# LTC5584.net
KiCad netlist of a schematic drawn in Altium Designer
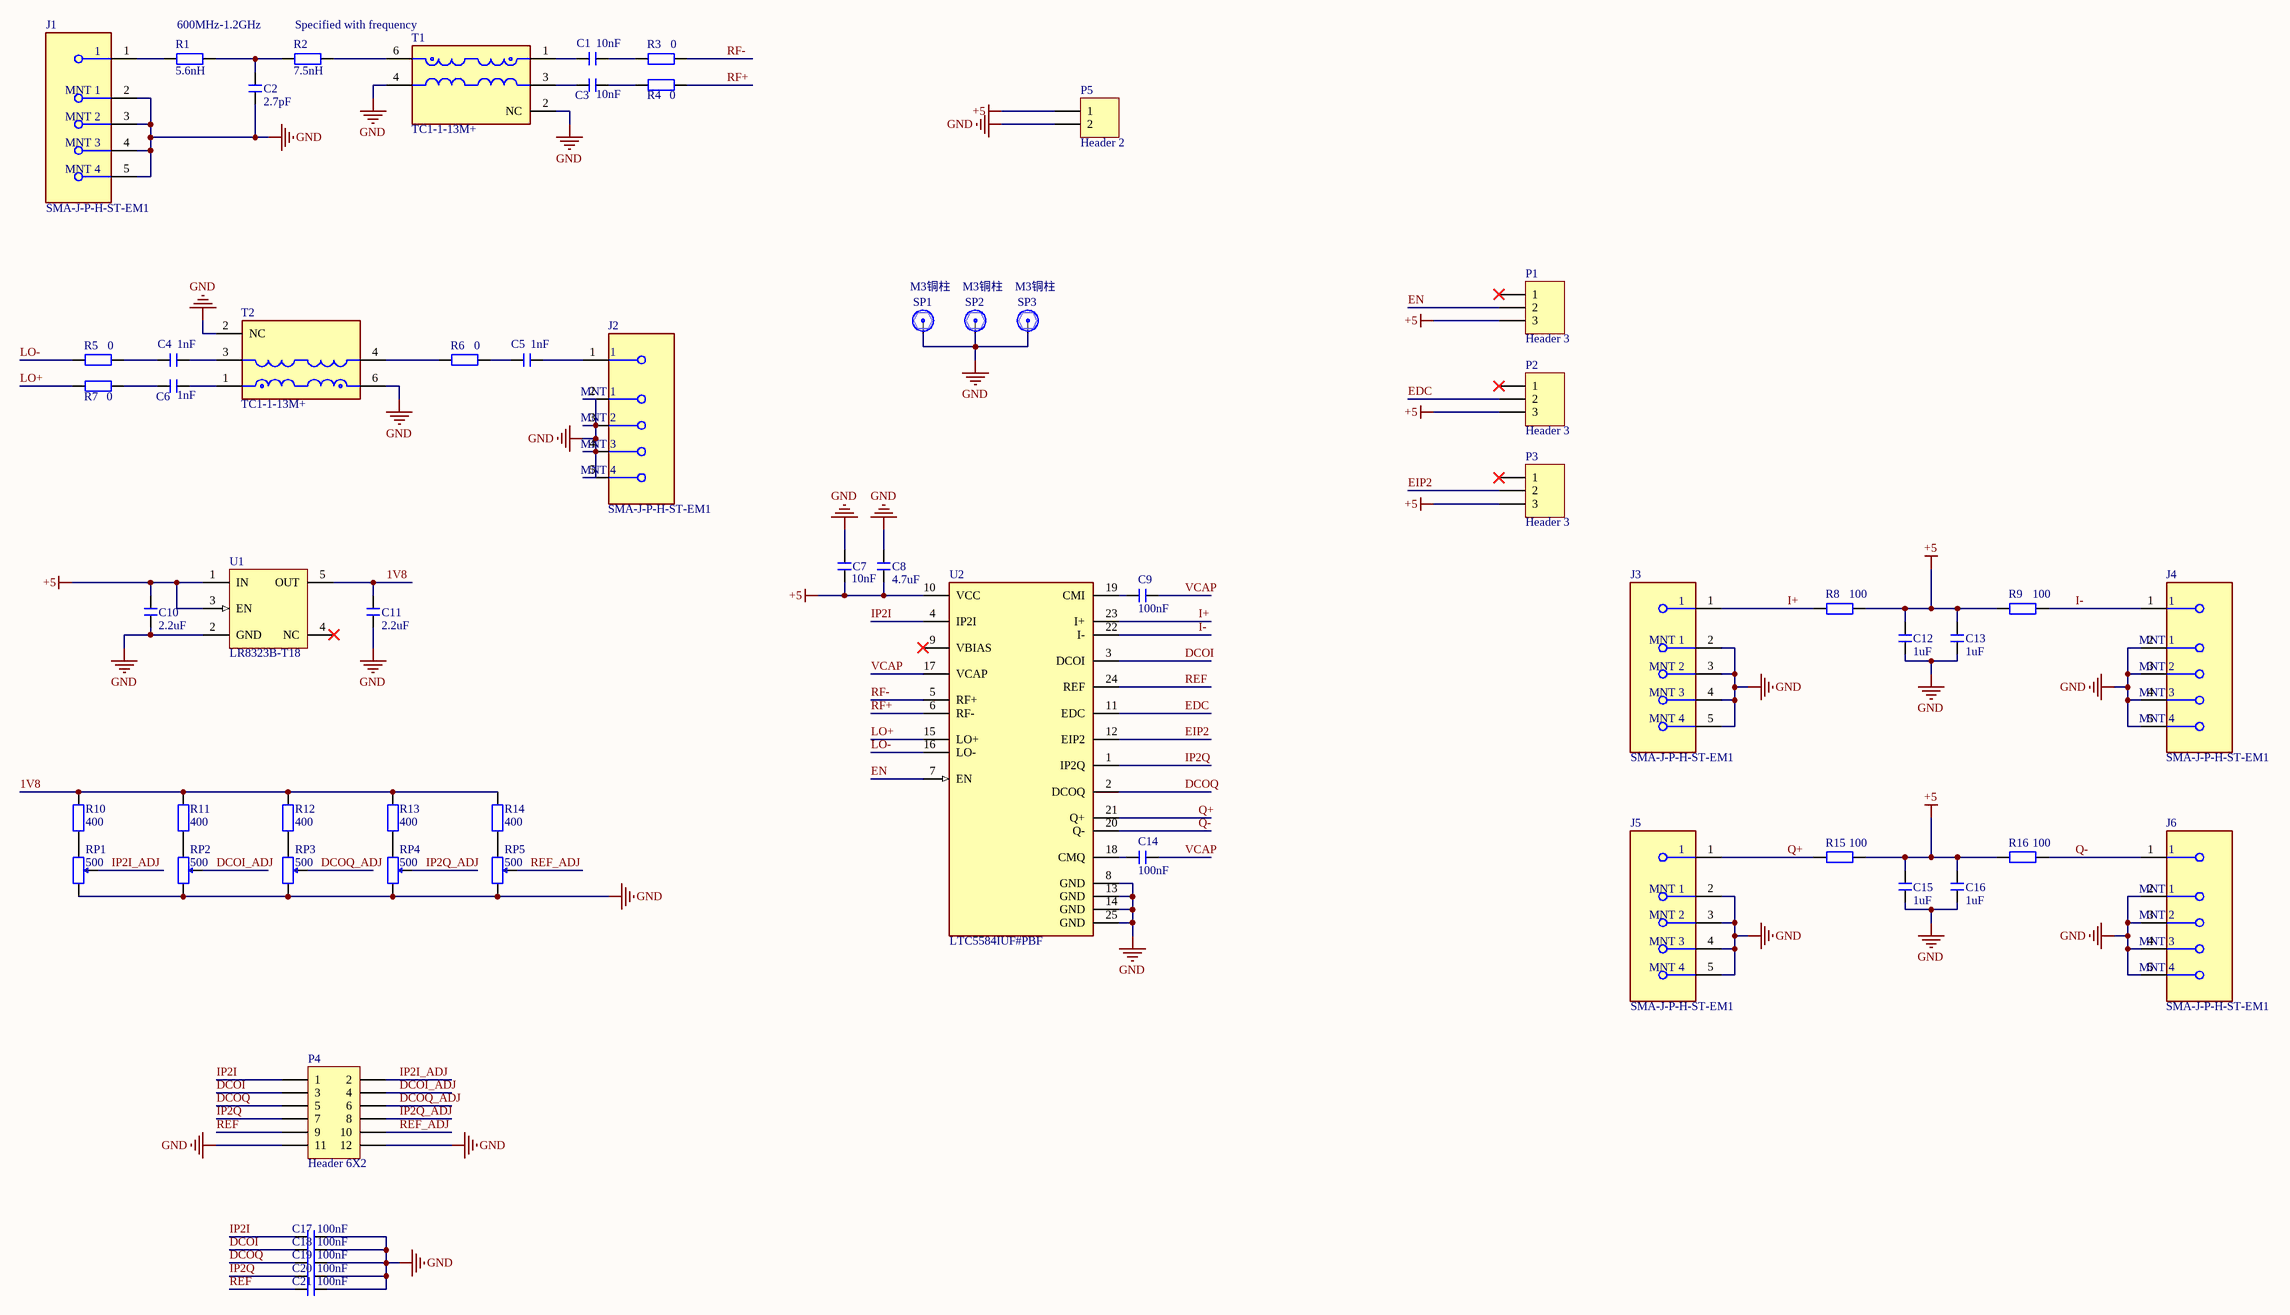
[diagram p0: LTC5584.SchDoc]

(export (version "E")
  (design (tool "Eeschema 10.0.6"))
  (components
    (comp (ref "C1")
      (value "10nF")
      (footprint "C 0402_L")
      (description "贴片电容")
      (libsource (lib "01 - 电容-电阻-电感") (part "C"))
    )
    (comp (ref "C2")
      (value "2.7pF")
      (footprint "C 0402_L")
      (description "贴片电容")
      (libsource (lib "01 - 电容-电阻-电感") (part "C"))
    )
    (comp (ref "C3")
      (value "10nF")
      (footprint "C 0402_L")
      (description "贴片电容")
      (libsource (lib "01 - 电容-电阻-电感") (part "C"))
    )
    (comp (ref "C4")
      (value "1nF")
      (footprint "C 0402_L")
      (description "贴片电容")
      (libsource (lib "01 - 电容-电阻-电感") (part "C"))
    )
    (comp (ref "C5")
      (value "1nF")
      (footprint "C 0402_L")
      (description "贴片电容")
      (libsource (lib "01 - 电容-电阻-电感") (part "C"))
    )
    (comp (ref "C6")
      (value "1nF")
      (footprint "C 0402_L")
      (description "贴片电容")
      (libsource (lib "01 - 电容-电阻-电感") (part "C"))
    )
    (comp (ref "C7")
      (value "10nF")
      (footprint "C 0402_L")
      (description "贴片电容")
      (libsource (lib "01 - 电容-电阻-电感") (part "C"))
    )
    (comp (ref "C8")
      (value "4.7uF")
      (footprint "C 0603_L")
      (description "贴片电容")
      (libsource (lib "01 - 电容-电阻-电感") (part "C"))
    )
    (comp (ref "C9")
      (value "100nF")
      (footprint "C 0402_L")
      (description "贴片电容")
      (libsource (lib "01 - 电容-电阻-电感") (part "C"))
    )
    (comp (ref "C10")
      (value "2.2uF")
      (footprint "C 0603_L")
      (description "贴片电容")
      (libsource (lib "01 - 电容-电阻-电感") (part "C"))
    )
    (comp (ref "C11")
      (value "2.2uF")
      (footprint "C 0603_L")
      (description "贴片电容")
      (libsource (lib "01 - 电容-电阻-电感") (part "C"))
    )
    (comp (ref "C12")
      (value "1uF")
      (footprint "C 0402_L")
      (description "贴片电容")
      (libsource (lib "01 - 电容-电阻-电感") (part "C"))
    )
    (comp (ref "C13")
      (value "1uF")
      (footprint "C 0402_L")
      (description "贴片电容")
      (libsource (lib "01 - 电容-电阻-电感") (part "C"))
    )
    (comp (ref "C14")
      (value "100nF")
      (footprint "C 0402_L")
      (description "贴片电容")
      (libsource (lib "01 - 电容-电阻-电感") (part "C"))
    )
    (comp (ref "C15")
      (value "1uF")
      (footprint "C 0402_L")
      (description "贴片电容")
      (libsource (lib "01 - 电容-电阻-电感") (part "C"))
    )
    (comp (ref "C16")
      (value "1uF")
      (footprint "C 0402_L")
      (description "贴片电容")
      (libsource (lib "01 - 电容-电阻-电感") (part "C"))
    )
    (comp (ref "C17")
      (value "100nF")
      (footprint "C 0402_L")
      (description "贴片电容")
      (libsource (lib "01 - 电容-电阻-电感") (part "C"))
    )
    (comp (ref "C18")
      (value "100nF")
      (footprint "C 0402_L")
      (description "贴片电容")
      (libsource (lib "01 - 电容-电阻-电感") (part "C"))
    )
    (comp (ref "C19")
      (value "100nF")
      (footprint "C 0402_L")
      (description "贴片电容")
      (libsource (lib "01 - 电容-电阻-电感") (part "C"))
    )
    (comp (ref "C20")
      (value "100nF")
      (footprint "C 0402_L")
      (description "贴片电容")
      (libsource (lib "01 - 电容-电阻-电感") (part "C"))
    )
    (comp (ref "C21")
      (value "100nF")
      (footprint "C 0402_L")
      (description "贴片电容")
      (libsource (lib "01 - 电容-电阻-电感") (part "C"))
    )
    (comp (ref "J1")
      (value "SMA-J-P-H-ST-EM1")
      (footprint "FP-SMA-J-P-H-ST-EM1-MFG")
      (description "CONN SMA JACK STR 50OHM EDGE MNT")
      (libsource (lib "Altium Content Vault") (part "c65b8a639cdaef1819ea20b5466f8fa"))
    )
    (comp (ref "J2")
      (value "SMA-J-P-H-ST-EM1")
      (footprint "FP-SMA-J-P-H-ST-EM1-MFG")
      (description "CONN SMA JACK STR 50OHM EDGE MNT")
      (libsource (lib "") (part "c65b8a639cdaef1819ea20b5466f8fa_1"))
    )
    (comp (ref "J3")
      (value "SMA-J-P-H-ST-EM1")
      (footprint "FP-SMA-J-P-H-ST-EM1-MFG")
      (description "CONN SMA JACK STR 50OHM EDGE MNT")
      (libsource (lib "Altium Content Vault") (part "c65b8a639cdaef1819ea20b5466f8fa"))
    )
    (comp (ref "J4")
      (value "SMA-J-P-H-ST-EM1")
      (footprint "FP-SMA-J-P-H-ST-EM1-MFG")
      (description "CONN SMA JACK STR 50OHM EDGE MNT")
      (libsource (lib "") (part "c65b8a639cdaef1819ea20b5466f8fa_1"))
    )
    (comp (ref "J5")
      (value "SMA-J-P-H-ST-EM1")
      (footprint "FP-SMA-J-P-H-ST-EM1-MFG")
      (description "CONN SMA JACK STR 50OHM EDGE MNT")
      (libsource (lib "Altium Content Vault") (part "c65b8a639cdaef1819ea20b5466f8fa"))
    )
    (comp (ref "J6")
      (value "SMA-J-P-H-ST-EM1")
      (footprint "FP-SMA-J-P-H-ST-EM1-MFG")
      (description "CONN SMA JACK STR 50OHM EDGE MNT")
      (libsource (lib "") (part "c65b8a639cdaef1819ea20b5466f8fa_1"))
    )
    (comp (ref "P1")
      (value "Header 3")
      (footprint "HDR1X3")
      (description "Header, 3-Pin")
      (fields (field (name "PUBLISHER") "Altium Limited"))
      (libsource (lib "Miscellaneous Connectors") (part "Header 3"))
    )
    (comp (ref "P2")
      (value "Header 3")
      (footprint "HDR1X3")
      (description "Header, 3-Pin")
      (fields (field (name "PUBLISHER") "Altium Limited"))
      (libsource (lib "Miscellaneous Connectors") (part "Header 3"))
    )
    (comp (ref "P3")
      (value "Header 3")
      (footprint "HDR1X3")
      (description "Header, 3-Pin")
      (fields (field (name "PUBLISHER") "Altium Limited"))
      (libsource (lib "Miscellaneous Connectors") (part "Header 3"))
    )
    (comp (ref "P4")
      (value "Header 6X2")
      (footprint "HDR2X6")
      (description "Header, 6-Pin, Dual row")
      (fields (field (name "PUBLISHER") "Altium Limited"))
      (libsource (lib "Miscellaneous Connectors") (part "Header 6X2"))
    )
    (comp (ref "P5")
      (value "Header 2")
      (footprint "HDR1X2")
      (description "Header, 2-Pin")
      (fields (field (name "PUBLISHER") "Altium Limited"))
      (libsource (lib "Miscellaneous Connectors") (part "Header 2"))
    )
    (comp (ref "R1")
      (value "5.6nH")
      (footprint "R 0402_L")
      (description "贴片电阻")
      (libsource (lib "01 - 电容-电阻-电感") (part "R"))
    )
    (comp (ref "R2")
      (value "7.5nH")
      (footprint "R 0402_L")
      (description "贴片电阻")
      (libsource (lib "01 - 电容-电阻-电感") (part "R"))
    )
    (comp (ref "R3")
      (value "0")
      (footprint "R 0402_L")
      (description "贴片电阻")
      (libsource (lib "01 - 电容-电阻-电感") (part "R"))
    )
    (comp (ref "R4")
      (value "0")
      (footprint "R 0402_L")
      (description "贴片电阻")
      (libsource (lib "01 - 电容-电阻-电感") (part "R"))
    )
    (comp (ref "R5")
      (value "0")
      (footprint "R 0402_L")
      (description "贴片电阻")
      (libsource (lib "01 - 电容-电阻-电感") (part "R"))
    )
    (comp (ref "R6")
      (value "0")
      (footprint "R 0402_L")
      (description "贴片电阻")
      (libsource (lib "01 - 电容-电阻-电感") (part "R"))
    )
    (comp (ref "R7")
      (value "0")
      (footprint "R 0402_L")
      (description "贴片电阻")
      (libsource (lib "01 - 电容-电阻-电感") (part "R"))
    )
    (comp (ref "R8")
      (value "100")
      (footprint "R 0402_L")
      (description "贴片电阻")
      (libsource (lib "01 - 电容-电阻-电感") (part "R"))
    )
    (comp (ref "R9")
      (value "100")
      (footprint "R 0402_L")
      (description "贴片电阻")
      (libsource (lib "01 - 电容-电阻-电感") (part "R"))
    )
    (comp (ref "R10")
      (value "400")
      (footprint "R 0603_L")
      (description "贴片电阻")
      (libsource (lib "01 - 电容-电阻-电感") (part "R"))
    )
    (comp (ref "R11")
      (value "400")
      (footprint "R 0603_L")
      (description "贴片电阻")
      (libsource (lib "01 - 电容-电阻-电感") (part "R"))
    )
    (comp (ref "R12")
      (value "400")
      (footprint "R 0603_L")
      (description "贴片电阻")
      (libsource (lib "01 - 电容-电阻-电感") (part "R"))
    )
    (comp (ref "R13")
      (value "400")
      (footprint "R 0603_L")
      (description "贴片电阻")
      (libsource (lib "01 - 电容-电阻-电感") (part "R"))
    )
    (comp (ref "R14")
      (value "400")
      (footprint "R 0603_L")
      (description "贴片电阻")
      (libsource (lib "01 - 电容-电阻-电感") (part "R"))
    )
    (comp (ref "R15")
      (value "100")
      (footprint "R 0402_L")
      (description "贴片电阻")
      (libsource (lib "01 - 电容-电阻-电感") (part "R"))
    )
    (comp (ref "R16")
      (value "100")
      (footprint "R 0402_L")
      (description "贴片电阻")
      (libsource (lib "01 - 电容-电阻-电感") (part "R"))
    )
    (comp (ref "RP1")
      (value "500")
      (footprint "3303W")
      (description "贴片电位器")
      (libsource (lib "01 - 电容-电阻-电感") (part "RP-SMD"))
    )
    (comp (ref "RP2")
      (value "500")
      (footprint "3303W")
      (description "贴片电位器")
      (libsource (lib "01 - 电容-电阻-电感") (part "RP-SMD"))
    )
    (comp (ref "RP3")
      (value "500")
      (footprint "3303W")
      (description "贴片电位器")
      (libsource (lib "01 - 电容-电阻-电感") (part "RP-SMD"))
    )
    (comp (ref "RP4")
      (value "500")
      (footprint "3303W")
      (description "贴片电位器")
      (libsource (lib "01 - 电容-电阻-电感") (part "RP-SMD"))
    )
    (comp (ref "RP5")
      (value "500")
      (footprint "3303W")
      (description "贴片电位器")
      (libsource (lib "01 - 电容-电阻-电感") (part "RP-SMD"))
    )
    (comp (ref "SP1")
      (value "M3铜柱")
      (footprint "M3x4_N")
      (description "铜柱")
      (libsource (lib "10 - 未分类元器件") (part "铜柱大焊盘"))
    )
    (comp (ref "SP2")
      (value "M3铜柱")
      (footprint "M3x4_N")
      (description "铜柱")
      (libsource (lib "10 - 未分类元器件") (part "铜柱大焊盘"))
    )
    (comp (ref "SP3")
      (value "M3铜柱")
      (footprint "M3x4_N")
      (description "铜柱")
      (libsource (lib "10 - 未分类元器件") (part "铜柱大焊盘"))
    )
    (comp (ref "T1")
      (value "TC1-1-13M+")
      (footprint "FP-TC1-1-13M+-MFG")
      (description "RF Transformer Surface Mount 50Ω 4.5 to 3000 MHz")
      (fields
        (field (name "OCTOPART") "https://octopart.com/tc1-1-13m%2B-mini-circuits-3993639")
        (field (name "MANUFACTURER") "Mini-Circuits")
      )
      (libsource (lib "") (part "bfcd2037c1656edfb93934ecf7289be_1"))
    )
    (comp (ref "T2")
      (value "TC1-1-13M+")
      (footprint "FP-TC1-1-13M+-MFG")
      (description "RF Transformer Surface Mount 50Ω 4.5 to 3000 MHz")
      (fields
        (field (name "OCTOPART") "https://octopart.com/tc1-1-13m%2B-mini-circuits-3993639")
        (field (name "MANUFACTURER") "Mini-Circuits")
      )
      (libsource (lib "Altium Content Vault") (part "bfcd2037c1656edfb93934ecf7289be"))
    )
    (comp (ref "U1")
      (value "LR8323B-T18")
      (footprint "DBV0005A_L")
      (description "None")
      (libsource (lib "LR8323B-T18") (part "LR8323B-T18"))
    )
    (comp (ref "U2")
      (value "LTC5584IUF#PBF")
      (footprint "FP-UF-24-05-08-1697-IPC_A")
      (description "RF DEMOD IC 30MHZ-1.4GHZ 24QFN")
      (libsource (lib "Altium Content Vault") (part "13c20dee0d392fadbe0d847c607ae3a"))
    )
  )
  (nets
    (net (code "1") (name "+5") (class "Default")
      (node (ref "C10") (pin "2") (pinfunction "2_2") (pintype "passive"))
      (node (ref "C12") (pin "2") (pinfunction "2_2") (pintype "passive"))
      (node (ref "C13") (pin "2") (pinfunction "2_2") (pintype "passive"))
      (node (ref "C15") (pin "2") (pinfunction "2_2") (pintype "passive"))
      (node (ref "C16") (pin "2") (pinfunction "2_2") (pintype "passive"))
      (node (ref "C7") (pin "1") (pinfunction "1_1") (pintype "passive"))
      (node (ref "C8") (pin "1") (pinfunction "1_1") (pintype "passive"))
      (node (ref "P1") (pin "3") (pinfunction "3_3") (pintype "passive"))
      (node (ref "P2") (pin "3") (pinfunction "3_3") (pintype "passive"))
      (node (ref "P3") (pin "3") (pinfunction "3_3") (pintype "passive"))
      (node (ref "P5") (pin "1") (pinfunction "1_1") (pintype "passive"))
      (node (ref "R15") (pin "2") (pinfunction "2_2") (pintype "passive"))
      (node (ref "R16") (pin "1") (pinfunction "1_1") (pintype "passive"))
      (node (ref "R8") (pin "2") (pinfunction "2_2") (pintype "passive"))
      (node (ref "R9") (pin "1") (pinfunction "1_1") (pintype "passive"))
      (node (ref "U1") (pin "1") (pinfunction "IN_1") (pintype "power_in"))
      (node (ref "U1") (pin "3") (pinfunction "EN_3") (pintype "input"))
      (node (ref "U2") (pin "10") (pinfunction "VCC_10") (pintype "power_in"))
    )
    (net (code "2") (name "/1V8") (class "Default")
      (node (ref "C11") (pin "2") (pinfunction "2_2") (pintype "passive"))
      (node (ref "R10") (pin "2") (pinfunction "2_2") (pintype "passive"))
      (node (ref "R11") (pin "2") (pinfunction "2_2") (pintype "passive"))
      (node (ref "R12") (pin "2") (pinfunction "2_2") (pintype "passive"))
      (node (ref "R13") (pin "2") (pinfunction "2_2") (pintype "passive"))
      (node (ref "R14") (pin "2") (pinfunction "2_2") (pintype "passive"))
      (node (ref "U1") (pin "5") (pinfunction "OUT_5") (pintype "power_in"))
    )
    (net (code "3") (name "/DCOI") (class "Default")
      (node (ref "C18") (pin "1") (pinfunction "1_1") (pintype "passive"))
      (node (ref "P4") (pin "3") (pinfunction "3_3") (pintype "passive"))
      (node (ref "U2") (pin "3") (pinfunction "DCOI_3") (pintype "passive"))
    )
    (net (code "4") (name "/DCOI_ADJ") (class "Default")
      (node (ref "P4") (pin "4") (pinfunction "4_4") (pintype "passive"))
      (node (ref "RP2") (pin "2") (pinfunction "2_2") (pintype "passive"))
    )
    (net (code "5") (name "/DCOQ") (class "Default")
      (node (ref "C19") (pin "1") (pinfunction "1_1") (pintype "passive"))
      (node (ref "P4") (pin "5") (pinfunction "5_5") (pintype "passive"))
      (node (ref "U2") (pin "2") (pinfunction "DCOQ_2") (pintype "passive"))
    )
    (net (code "6") (name "/DCOQ_ADJ") (class "Default")
      (node (ref "P4") (pin "6") (pinfunction "6_6") (pintype "passive"))
      (node (ref "RP3") (pin "2") (pinfunction "2_2") (pintype "passive"))
    )
    (net (code "7") (name "/EDC") (class "Default")
      (node (ref "P2") (pin "2") (pinfunction "2_2") (pintype "passive"))
      (node (ref "U2") (pin "11") (pinfunction "EDC_11") (pintype "passive"))
    )
    (net (code "8") (name "/EIP2") (class "Default")
      (node (ref "P3") (pin "2") (pinfunction "2_2") (pintype "passive"))
      (node (ref "U2") (pin "12") (pinfunction "EIP2_12") (pintype "passive"))
    )
    (net (code "9") (name "/EN") (class "Default")
      (node (ref "P1") (pin "2") (pinfunction "2_2") (pintype "passive"))
      (node (ref "U2") (pin "7") (pinfunction "EN_7") (pintype "input"))
    )
    (net (code "10") (name "/I+") (class "Default")
      (node (ref "J3") (pin "1") (pinfunction "1_1") (pintype "passive"))
      (node (ref "R8") (pin "1") (pinfunction "1_1") (pintype "passive"))
      (node (ref "U2") (pin "23") (pinfunction "I+_23") (pintype "passive"))
    )
    (net (code "11") (name "/I-") (class "Default")
      (node (ref "J4") (pin "1") (pinfunction "1_1") (pintype "passive"))
      (node (ref "R9") (pin "2") (pinfunction "2_2") (pintype "passive"))
      (node (ref "U2") (pin "22") (pinfunction "I-_22") (pintype "passive"))
    )
    (net (code "12") (name "/IP2I") (class "Default")
      (node (ref "C17") (pin "1") (pinfunction "1_1") (pintype "passive"))
      (node (ref "P4") (pin "1") (pinfunction "1_1") (pintype "passive"))
      (node (ref "U2") (pin "4") (pinfunction "IP2I_4") (pintype "passive"))
    )
    (net (code "13") (name "/IP2I_ADJ") (class "Default")
      (node (ref "P4") (pin "2") (pinfunction "2_2") (pintype "passive"))
      (node (ref "RP1") (pin "2") (pinfunction "2_2") (pintype "passive"))
    )
    (net (code "14") (name "/IP2Q") (class "Default")
      (node (ref "C20") (pin "1") (pinfunction "1_1") (pintype "passive"))
      (node (ref "P4") (pin "7") (pinfunction "7_7") (pintype "passive"))
      (node (ref "U2") (pin "1") (pinfunction "IP2Q_1") (pintype "passive"))
    )
    (net (code "15") (name "/IP2Q_ADJ") (class "Default")
      (node (ref "P4") (pin "8") (pinfunction "8_8") (pintype "passive"))
      (node (ref "RP4") (pin "2") (pinfunction "2_2") (pintype "passive"))
    )
    (net (code "16") (name "/LO+") (class "Default")
      (node (ref "R7") (pin "1") (pinfunction "1_1") (pintype "passive"))
      (node (ref "U2") (pin "15") (pinfunction "LO+_15") (pintype "passive"))
    )
    (net (code "17") (name "/LO-") (class "Default")
      (node (ref "R5") (pin "1") (pinfunction "1_1") (pintype "passive"))
      (node (ref "U2") (pin "16") (pinfunction "LO-_16") (pintype "passive"))
    )
    (net (code "18") (name "/Q+") (class "Default")
      (node (ref "J5") (pin "1") (pinfunction "1_1") (pintype "passive"))
      (node (ref "R15") (pin "1") (pinfunction "1_1") (pintype "passive"))
      (node (ref "U2") (pin "21") (pinfunction "Q+_21") (pintype "passive"))
    )
    (net (code "19") (name "/Q-") (class "Default")
      (node (ref "J6") (pin "1") (pinfunction "1_1") (pintype "passive"))
      (node (ref "R16") (pin "2") (pinfunction "2_2") (pintype "passive"))
      (node (ref "U2") (pin "20") (pinfunction "Q-_20") (pintype "passive"))
    )
    (net (code "20") (name "/REF") (class "Default")
      (node (ref "C21") (pin "1") (pinfunction "1_1") (pintype "passive"))
      (node (ref "P4") (pin "9") (pinfunction "9_9") (pintype "passive"))
      (node (ref "U2") (pin "24") (pinfunction "REF_24") (pintype "passive"))
    )
    (net (code "21") (name "/REF_ADJ") (class "Default")
      (node (ref "P4") (pin "10") (pinfunction "10_10") (pintype "passive"))
      (node (ref "RP5") (pin "2") (pinfunction "2_2") (pintype "passive"))
    )
    (net (code "22") (name "/RF+") (class "Default")
      (node (ref "R4") (pin "2") (pinfunction "2_2") (pintype "passive"))
      (node (ref "U2") (pin "6") (pinfunction "RF-_6") (pintype "passive"))
    )
    (net (code "23") (name "/RF-") (class "Default")
      (node (ref "R3") (pin "2") (pinfunction "2_2") (pintype "passive"))
      (node (ref "U2") (pin "5") (pinfunction "RF+_5") (pintype "passive"))
    )
    (net (code "24") (name "/VCAP") (class "Default")
      (node (ref "C14") (pin "1") (pinfunction "1_1") (pintype "passive"))
      (node (ref "C9") (pin "1") (pinfunction "1_1") (pintype "passive"))
      (node (ref "U2") (pin "17") (pinfunction "VCAP_17") (pintype "power_in"))
    )
    (net (code "25") (name "GND") (class "Default")
      (node (ref "C10") (pin "1") (pinfunction "1_1") (pintype "passive"))
      (node (ref "C11") (pin "1") (pinfunction "1_1") (pintype "passive"))
      (node (ref "C12") (pin "1") (pinfunction "1_1") (pintype "passive"))
      (node (ref "C13") (pin "1") (pinfunction "1_1") (pintype "passive"))
      (node (ref "C15") (pin "1") (pinfunction "1_1") (pintype "passive"))
      (node (ref "C16") (pin "1") (pinfunction "1_1") (pintype "passive"))
      (node (ref "C17") (pin "2") (pinfunction "2_2") (pintype "passive"))
      (node (ref "C18") (pin "2") (pinfunction "2_2") (pintype "passive"))
      (node (ref "C19") (pin "2") (pinfunction "2_2") (pintype "passive"))
      (node (ref "C2") (pin "1") (pinfunction "1_1") (pintype "passive"))
      (node (ref "C20") (pin "2") (pinfunction "2_2") (pintype "passive"))
      (node (ref "C21") (pin "2") (pinfunction "2_2") (pintype "passive"))
      (node (ref "C7") (pin "2") (pinfunction "2_2") (pintype "passive"))
      (node (ref "C8") (pin "2") (pinfunction "2_2") (pintype "passive"))
      (node (ref "J1") (pin "2") (pinfunction "MNT_1_2") (pintype "passive"))
      (node (ref "J1") (pin "3") (pinfunction "MNT_2_3") (pintype "passive"))
      (node (ref "J1") (pin "4") (pinfunction "MNT_3_4") (pintype "passive"))
      (node (ref "J1") (pin "5") (pinfunction "MNT_4_5") (pintype "passive"))
      (node (ref "J2") (pin "2") (pinfunction "MNT_1_2") (pintype "passive"))
      (node (ref "J2") (pin "3") (pinfunction "MNT_2_3") (pintype "passive"))
      (node (ref "J2") (pin "4") (pinfunction "MNT_3_4") (pintype "passive"))
      (node (ref "J2") (pin "5") (pinfunction "MNT_4_5") (pintype "passive"))
      (node (ref "J3") (pin "2") (pinfunction "MNT_1_2") (pintype "passive"))
      (node (ref "J3") (pin "3") (pinfunction "MNT_2_3") (pintype "passive"))
      (node (ref "J3") (pin "4") (pinfunction "MNT_3_4") (pintype "passive"))
      (node (ref "J3") (pin "5") (pinfunction "MNT_4_5") (pintype "passive"))
      (node (ref "J4") (pin "2") (pinfunction "MNT_1_2") (pintype "passive"))
      (node (ref "J4") (pin "3") (pinfunction "MNT_2_3") (pintype "passive"))
      (node (ref "J4") (pin "4") (pinfunction "MNT_3_4") (pintype "passive"))
      (node (ref "J4") (pin "5") (pinfunction "MNT_4_5") (pintype "passive"))
      (node (ref "J5") (pin "2") (pinfunction "MNT_1_2") (pintype "passive"))
      (node (ref "J5") (pin "3") (pinfunction "MNT_2_3") (pintype "passive"))
      (node (ref "J5") (pin "4") (pinfunction "MNT_3_4") (pintype "passive"))
      (node (ref "J5") (pin "5") (pinfunction "MNT_4_5") (pintype "passive"))
      (node (ref "J6") (pin "2") (pinfunction "MNT_1_2") (pintype "passive"))
      (node (ref "J6") (pin "3") (pinfunction "MNT_2_3") (pintype "passive"))
      (node (ref "J6") (pin "4") (pinfunction "MNT_3_4") (pintype "passive"))
      (node (ref "J6") (pin "5") (pinfunction "MNT_4_5") (pintype "passive"))
      (node (ref "P4") (pin "11") (pinfunction "11_11") (pintype "passive"))
      (node (ref "P4") (pin "12") (pinfunction "12_12") (pintype "passive"))
      (node (ref "P5") (pin "2") (pinfunction "2_2") (pintype "passive"))
      (node (ref "RP1") (pin "3") (pinfunction "3_3") (pintype "passive"))
      (node (ref "RP2") (pin "3") (pinfunction "3_3") (pintype "passive"))
      (node (ref "RP3") (pin "3") (pinfunction "3_3") (pintype "passive"))
      (node (ref "RP4") (pin "3") (pinfunction "3_3") (pintype "passive"))
      (node (ref "RP5") (pin "3") (pinfunction "3_3") (pintype "passive"))
      (node (ref "SP1") (pin "1") (pinfunction "1_1") (pintype "passive"))
      (node (ref "SP2") (pin "1") (pinfunction "1_1") (pintype "passive"))
      (node (ref "SP3") (pin "1") (pinfunction "1_1") (pintype "passive"))
      (node (ref "T1") (pin "2") (pinfunction "NC_2") (pintype "passive"))
      (node (ref "T1") (pin "4") (pinfunction "PRIMARY_4") (pintype "passive"))
      (node (ref "T2") (pin "2") (pinfunction "NC_2") (pintype "passive"))
      (node (ref "T2") (pin "6") (pinfunction "PRIMARY_DOT_6") (pintype "passive"))
      (node (ref "U1") (pin "2") (pinfunction "GND_2") (pintype "power_in"))
      (node (ref "U2") (pin "13") (pinfunction "GND_13") (pintype "power_in"))
      (node (ref "U2") (pin "14") (pinfunction "GND_14") (pintype "power_in"))
      (node (ref "U2") (pin "25") (pinfunction "GND_25") (pintype "power_in"))
      (node (ref "U2") (pin "8") (pinfunction "GND_8") (pintype "power_in"))
    )
    (net (code "26") (name "Net-(C1-Pad2)") (class "Default")
      (node (ref "C1") (pin "2") (pinfunction "2_2") (pintype "passive"))
      (node (ref "R3") (pin "1") (pinfunction "1_1") (pintype "passive"))
    )
    (net (code "27") (name "Net-(C2-Pad2)") (class "Default")
      (node (ref "C2") (pin "2") (pinfunction "2_2") (pintype "passive"))
      (node (ref "R1") (pin "2") (pinfunction "2_2") (pintype "passive"))
      (node (ref "R2") (pin "1") (pinfunction "1_1") (pintype "passive"))
    )
    (net (code "28") (name "Net-(C3-Pad2)") (class "Default")
      (node (ref "C3") (pin "2") (pinfunction "2_2") (pintype "passive"))
      (node (ref "R4") (pin "1") (pinfunction "1_1") (pintype "passive"))
    )
    (net (code "29") (name "Net-(C4-Pad1)") (class "Default")
      (node (ref "C4") (pin "1") (pinfunction "1_1") (pintype "passive"))
      (node (ref "R5") (pin "2") (pinfunction "2_2") (pintype "passive"))
    )
    (net (code "30") (name "Net-(C5-Pad1)") (class "Default")
      (node (ref "C5") (pin "1") (pinfunction "1_1") (pintype "passive"))
      (node (ref "R6") (pin "2") (pinfunction "2_2") (pintype "passive"))
    )
    (net (code "31") (name "Net-(C5-Pad2)") (class "Default")
      (node (ref "C5") (pin "2") (pinfunction "2_2") (pintype "passive"))
      (node (ref "J2") (pin "1") (pinfunction "1_1") (pintype "passive"))
    )
    (net (code "32") (name "Net-(C6-Pad1)") (class "Default")
      (node (ref "C6") (pin "1") (pinfunction "1_1") (pintype "passive"))
      (node (ref "R7") (pin "2") (pinfunction "2_2") (pintype "passive"))
    )
    (net (code "33") (name "Net-(J1-Pad1)") (class "Default")
      (node (ref "J1") (pin "1") (pinfunction "1_1") (pintype "passive"))
      (node (ref "R1") (pin "1") (pinfunction "1_1") (pintype "passive"))
    )
    (net (code "34") (name "Net-(R10-Pad1)") (class "Default")
      (node (ref "R10") (pin "1") (pinfunction "1_1") (pintype "passive"))
      (node (ref "RP1") (pin "1") (pinfunction "1_1") (pintype "passive"))
    )
    (net (code "35") (name "Net-(R11-Pad1)") (class "Default")
      (node (ref "R11") (pin "1") (pinfunction "1_1") (pintype "passive"))
      (node (ref "RP2") (pin "1") (pinfunction "1_1") (pintype "passive"))
    )
    (net (code "36") (name "Net-(R12-Pad1)") (class "Default")
      (node (ref "R12") (pin "1") (pinfunction "1_1") (pintype "passive"))
      (node (ref "RP3") (pin "1") (pinfunction "1_1") (pintype "passive"))
    )
    (net (code "37") (name "Net-(R13-Pad1)") (class "Default")
      (node (ref "R13") (pin "1") (pinfunction "1_1") (pintype "passive"))
      (node (ref "RP4") (pin "1") (pinfunction "1_1") (pintype "passive"))
    )
    (net (code "38") (name "Net-(R14-Pad1)") (class "Default")
      (node (ref "R14") (pin "1") (pinfunction "1_1") (pintype "passive"))
      (node (ref "RP5") (pin "1") (pinfunction "1_1") (pintype "passive"))
    )
    (net (code "39") (name "Net-(T1-PRIMARY_DOT)") (class "Default")
      (node (ref "R2") (pin "2") (pinfunction "2_2") (pintype "passive"))
      (node (ref "T1") (pin "6") (pinfunction "PRIMARY_DOT_6") (pintype "passive"))
    )
    (net (code "40") (name "Net-(T1-SECONDARY)") (class "Default")
      (node (ref "C3") (pin "1") (pinfunction "1_1") (pintype "passive"))
      (node (ref "T1") (pin "3") (pinfunction "SECONDARY_3") (pintype "passive"))
    )
    (net (code "41") (name "Net-(T1-SECONDARY_DOT)") (class "Default")
      (node (ref "C1") (pin "1") (pinfunction "1_1") (pintype "passive"))
      (node (ref "T1") (pin "1") (pinfunction "SECONDARY_DOT_1") (pintype "passive"))
    )
    (net (code "42") (name "Net-(T2-PRIMARY)") (class "Default")
      (node (ref "R6") (pin "1") (pinfunction "1_1") (pintype "passive"))
      (node (ref "T2") (pin "4") (pinfunction "PRIMARY_4") (pintype "passive"))
    )
    (net (code "43") (name "Net-(T2-SECONDARY)") (class "Default")
      (node (ref "C4") (pin "2") (pinfunction "2_2") (pintype "passive"))
      (node (ref "T2") (pin "3") (pinfunction "SECONDARY_3") (pintype "passive"))
    )
    (net (code "44") (name "Net-(T2-SECONDARY_DOT)") (class "Default")
      (node (ref "C6") (pin "2") (pinfunction "2_2") (pintype "passive"))
      (node (ref "T2") (pin "1") (pinfunction "SECONDARY_DOT_1") (pintype "passive"))
    )
    (net (code "45") (name "Net-(U2-CMI)") (class "Default")
      (node (ref "C9") (pin "2") (pinfunction "2_2") (pintype "passive"))
      (node (ref "U2") (pin "19") (pinfunction "CMI_19") (pintype "passive"))
    )
    (net (code "46") (name "Net-(U2-CMQ)") (class "Default")
      (node (ref "C14") (pin "2") (pinfunction "2_2") (pintype "passive"))
      (node (ref "U2") (pin "18") (pinfunction "CMQ_18") (pintype "passive"))
    )
    (net (code "47") (name "unconnected-(P1-Pad1)") (class "Default")
      (node (ref "P1") (pin "1") (pinfunction "1_1") (pintype "passive+no_connect"))
    )
    (net (code "48") (name "unconnected-(P2-Pad1)") (class "Default")
      (node (ref "P2") (pin "1") (pinfunction "1_1") (pintype "passive+no_connect"))
    )
    (net (code "49") (name "unconnected-(P3-Pad1)") (class "Default")
      (node (ref "P3") (pin "1") (pinfunction "1_1") (pintype "passive+no_connect"))
    )
    (net (code "50") (name "unconnected-(U1-NC-Pad4)") (class "Default")
      (node (ref "U1") (pin "4") (pinfunction "NC_4") (pintype "passive+no_connect"))
    )
    (net (code "51") (name "unconnected-(U2-VBIAS-Pad9)") (class "Default")
      (node (ref "U2") (pin "9") (pinfunction "VBIAS_9") (pintype "power_in+no_connect"))
    )
  )
)
